# uC_IO.net
KiCad netlist of a schematic drawn in Altium Designer
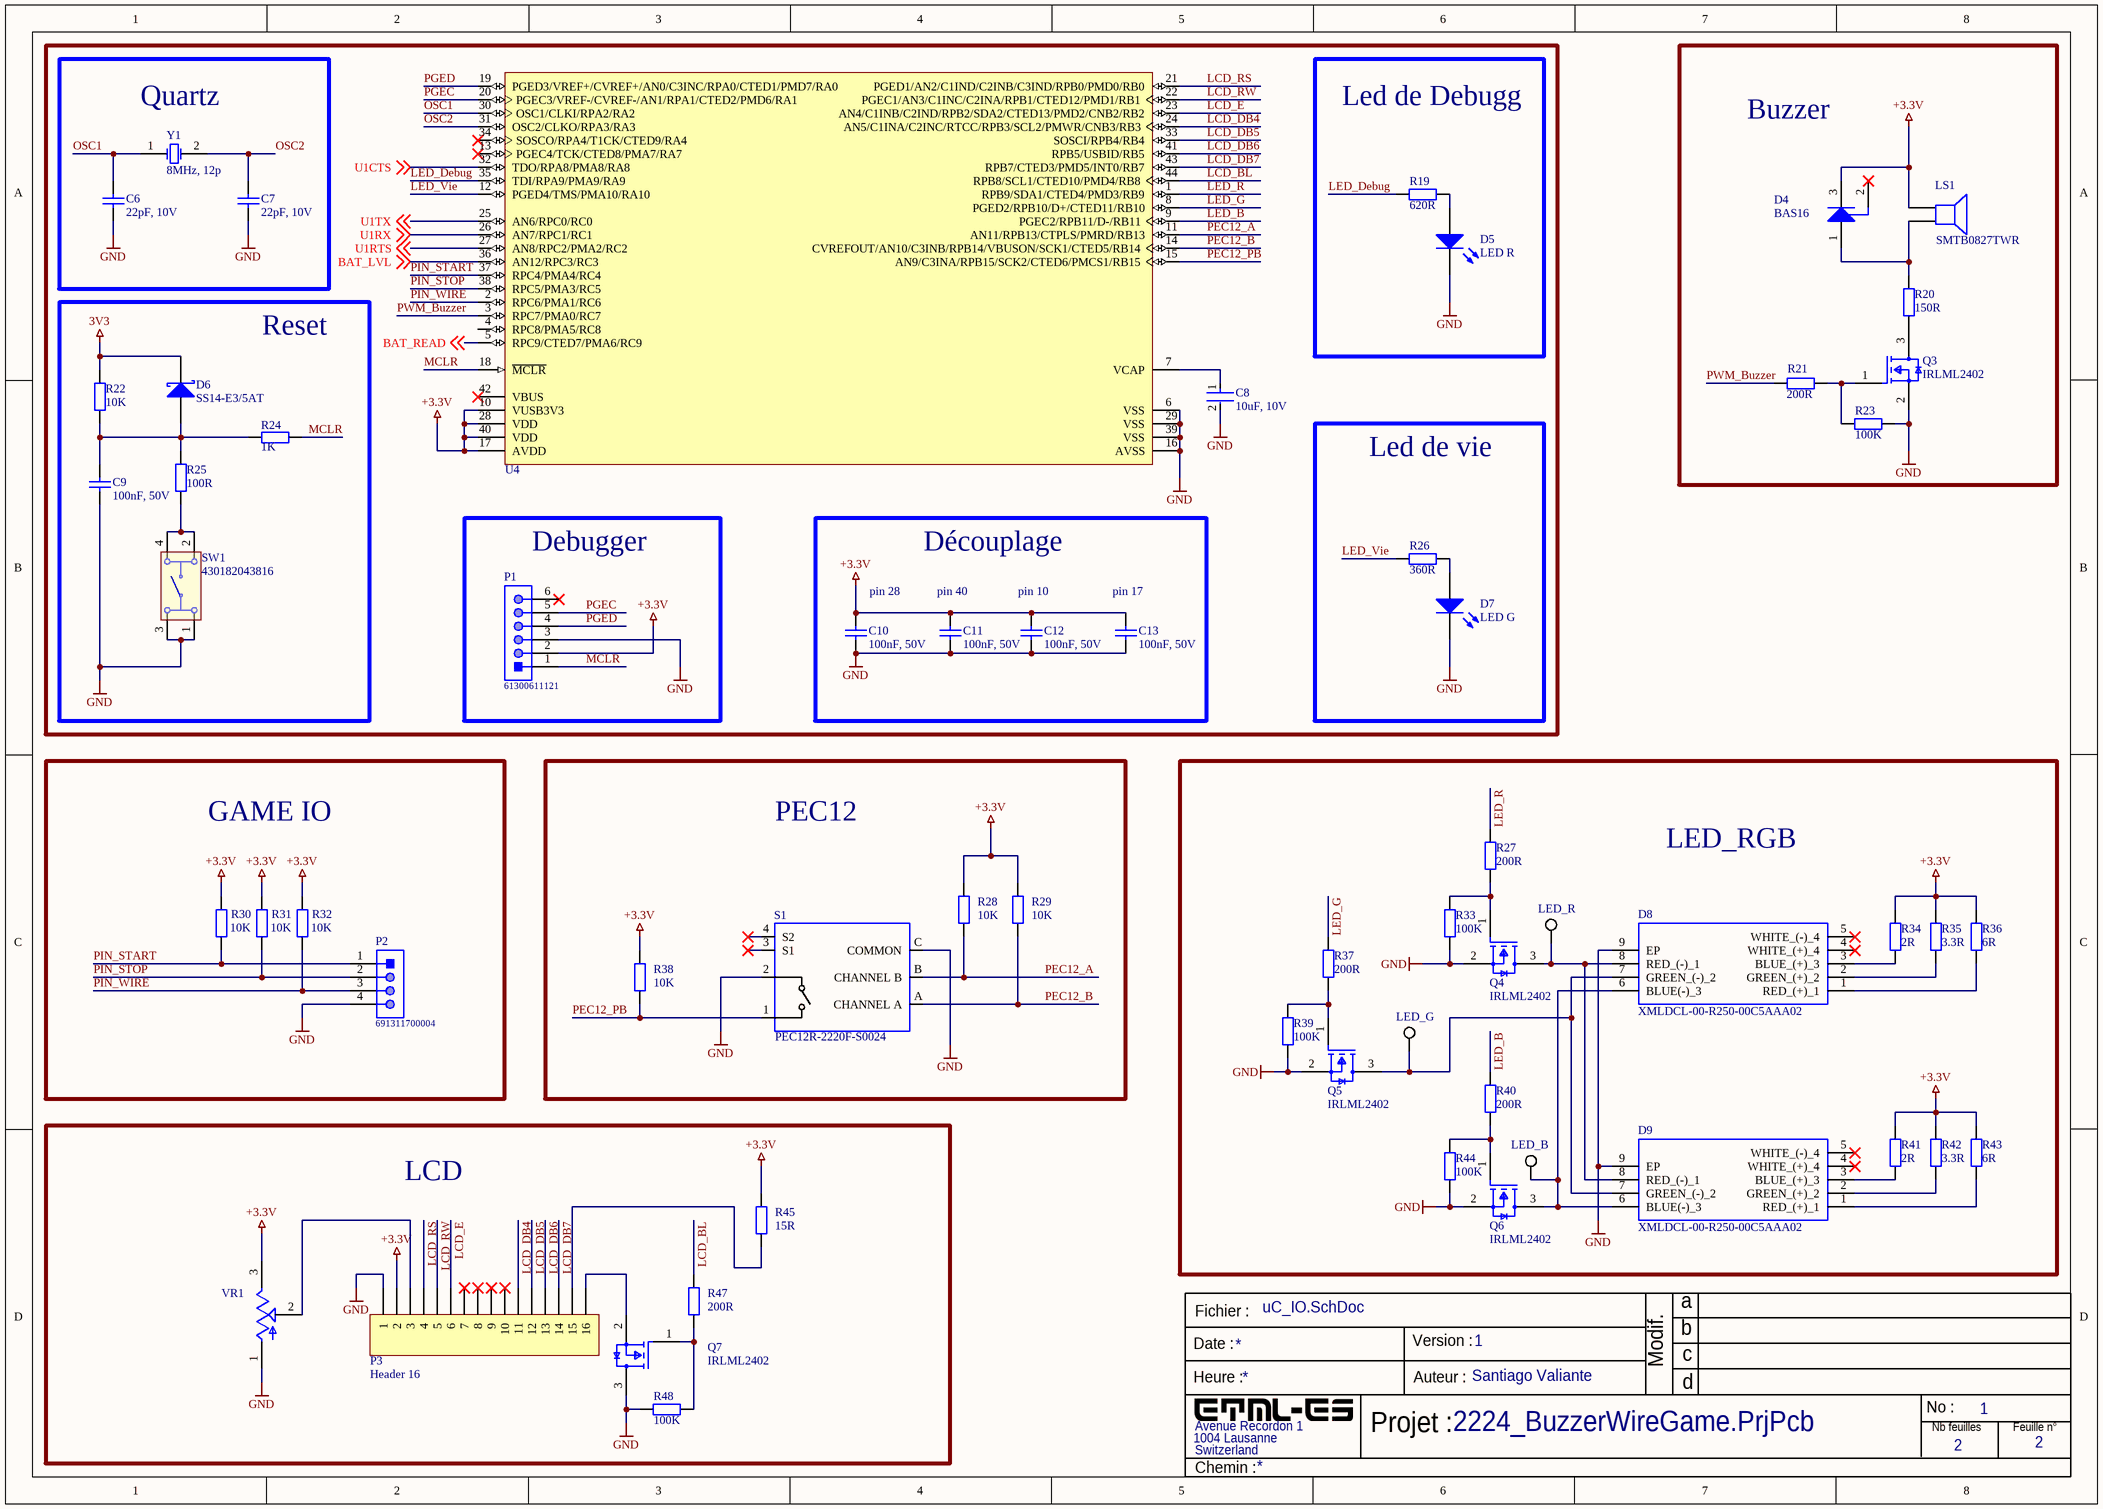
[diagram p0: uC_IO.SchDoc]

(export (version "E")
  (design (tool "Eeschema 10.0.6"))
  (components
    (comp (ref "C6")
      (value "22pF, 10V")
      (footprint "CAP_0805")
      (description "CAP 22pF 10V ±10% 0805 (2012 Metric) Thickness 0.75mm SMD")
      (fields (field (name "TOLERANCE") "Â±10%"))
      (libsource (lib "2121_Robot3roues_V2.0") (part "CAP"))
    )
    (comp (ref "C7")
      (value "22pF, 10V")
      (footprint "CAP_0805")
      (description "CAP 22pF 10V ±10% 0805 (2012 Metric) Thickness 0.75mm SMD")
      (fields (field (name "TOLERANCE") "Â±10%"))
      (libsource (lib "2121_Robot3roues_V2.0") (part "CAP"))
    )
    (comp (ref "C8")
      (value "10uF, 10V")
      (footprint "CAP_0805")
      (description "CAP CER 10UF 10V X5R 0805")
      (fields (field (name "TOLERANCE") "10%") (field (name "MANUFACTURER PART NUMBER") "C0805C106K8PACTU"))
      (libsource (lib "2121_Robot3roues_V2.0") (part "11868f565c42a9108669ba33697ecf6"))
    )
    (comp (ref "C9")
      (value "100nF, 50V")
      (footprint "CAP_0805")
      (description "WCAP-CSGP General Purpose Ceramic Capacitors, size 0805, 100nF, +/-10%, 50VDC")
      (fields (field (name "PART NUMBER") "885012207098") (field (name "PUBLISHER") "Wurth Elektronik"))
      (libsource (lib "VPA_v2b") (part "885012207098"))
    )
    (comp (ref "C10")
      (value "100nF, 50V")
      (footprint "CAP_0805")
      (description "WCAP-CSGP General Purpose Ceramic Capacitors, size 0805, 100nF, +/-10%, 50VDC")
      (fields (field (name "PART NUMBER") "885012207098") (field (name "PUBLISHER") "Wurth Elektronik"))
      (libsource (lib "VPA_v2b") (part "885012207098"))
    )
    (comp (ref "C11")
      (value "100nF, 50V")
      (footprint "CAP_0805")
      (description "WCAP-CSGP General Purpose Ceramic Capacitors, size 0805, 100nF, +/-10%, 50VDC")
      (fields (field (name "PART NUMBER") "885012207098") (field (name "PUBLISHER") "Wurth Elektronik"))
      (libsource (lib "VPA_v2b") (part "885012207098"))
    )
    (comp (ref "C12")
      (value "100nF, 50V")
      (footprint "CAP_0805")
      (description "WCAP-CSGP General Purpose Ceramic Capacitors, size 0805, 100nF, +/-10%, 50VDC")
      (fields (field (name "PART NUMBER") "885012207098") (field (name "PUBLISHER") "Wurth Elektronik"))
      (libsource (lib "VPA_v2b") (part "885012207098"))
    )
    (comp (ref "C13")
      (value "100nF, 50V")
      (footprint "CAP_0805")
      (description "WCAP-CSGP General Purpose Ceramic Capacitors, size 0805, 100nF, +/-10%, 50VDC")
      (fields (field (name "PART NUMBER") "885012207098") (field (name "PUBLISHER") "Wurth Elektronik"))
      (libsource (lib "VPA_v2b") (part "885012207098"))
    )
    (comp (ref "D4")
      (value "BAS16")
      (footprint "INF-SOT23_L")
      (description "Silicon Switching Diode, SOT23, Reel, Green")
      (fields (field (name "MANUFACTURER") "Infineon"))
      (libsource (lib "Altium Content Vault") (part "INF-D_A1K3-3"))
    )
    (comp (ref "D5")
      (value "LED R")
      (footprint "3.2X1.6X1.1")
      (description "Typical RED, GREEN, YELLOW, AMBER GaAs LED")
      (fields (field (name "PUBLISHER") "Altium Limited"))
      (libsource (lib "Miscellaneous Devices") (part "LED2"))
    )
    (comp (ref "D6")
      (value "SS14-E3/5AT")
      (footprint "VISH-DO-214AC-2_V")
      (fields (field (name "MANUFACTURER") "Vishay Semiconductor"))
      (libsource (lib "Altium Content Vault") (part "VISH-DSKY_A1K2-2"))
    )
    (comp (ref "D7")
      (value "LED G")
      (footprint "3.2X1.6X1.1")
      (description "Typical RED, GREEN, YELLOW, AMBER GaAs LED")
      (fields (field (name "PUBLISHER") "Altium Limited"))
      (libsource (lib "Miscellaneous Devices") (part "LED2"))
    )
    (comp (ref "D8")
      (value "XMLDCL-00-R250-00C5AAA02")
      (footprint "XMLDCL00R25000C5AAA02")
      (description "High Power LEDs - Multi-Colour RGB, White 6000K LED")
      (fields (field (name "MOUSER PART NUMBER") "941-XMLDCL0R25C5A02"))
      (libsource (lib "Projet_Lampe_V1") (part "XMLDCL-00-R250-00C5AAA02"))
    )
    (comp (ref "D9")
      (value "XMLDCL-00-R250-00C5AAA02")
      (footprint "XMLDCL00R25000C5AAA02")
      (description "High Power LEDs - Multi-Colour RGB, White 6000K LED")
      (fields (field (name "MOUSER PART NUMBER") "941-XMLDCL0R25C5A02"))
      (libsource (lib "Projet_Lampe_V1") (part "XMLDCL-00-R250-00C5AAA02"))
    )
    (comp (ref "LED_B")
      (value "Vbat")
      (footprint "KSTN-5019_V")
      (description "Test Point, 1 Position SMD, RoHS, Tape and Reel")
      (libsource (lib "Altium Content Vault") (part "TESTPOINT_WHITE"))
    )
    (comp (ref "LED_G")
      (value "Vbat")
      (footprint "KSTN-5019_V")
      (description "Test Point, 1 Position SMD, RoHS, Tape and Reel")
      (libsource (lib "Altium Content Vault") (part "TESTPOINT_WHITE"))
    )
    (comp (ref "LED_R")
      (value "Vbat")
      (footprint "KSTN-5019_V")
      (description "Test Point, 1 Position SMD, RoHS, Tape and Reel")
      (libsource (lib "Altium Content Vault") (part "TESTPOINT_WHITE"))
    )
    (comp (ref "LS1")
      (value "SMTB0827TWR")
      (footprint "XDCR_SMTB-0827-TW-R")
      (description "Loudspeaker")
      (fields (field (name "PUBLISHER") "Altium Limited"))
      (libsource (lib "Miscellaneous Devices") (part "Speaker"))
    )
    (comp (ref "P1")
      (value "61300611121")
      (footprint "61300611121")
      (description "THT Vertical Pin Header WR-PHD, Pitch 2.54 mm, Single Row, 6 pins")
      (fields (field (name "MANUFACTURER") "Wurth Elektronik") (field (name "PUBLISHER") "WurthElektronik"))
      (libsource (lib "Altium Content Vault") (part "WE-CN-1P-M-R6"))
    )
    (comp (ref "P2")
      (value "691311700004")
      (footprint "691311700004")
      (description "Serie 3117 - 5.00mm Open Vertical PCB Header WR-TBL, 4 pin")
      (fields (field (name "MANUFACTURER") "Wurth Elektronik") (field (name "PUBLISHER") "WurthElektronik"))
      (libsource (lib "Altium Content Vault") (part "WE-CN-1P-M-R4"))
    )
    (comp (ref "P3")
      (value "Header 16")
      (footprint "SHDR16W77P254_2X8_2764X859X1004P")
      (description "Header, 16-Pin")
      (fields (field (name "PUBLISHER") "Altium Limited"))
      (libsource (lib "Miscellaneous Connectors") (part "Header 16"))
    )
    (comp (ref "Q3")
      (value "IRLML2402")
      (footprint "FP-Micro3-IPC_B")
      (description "MOSFET N-CH 20V 1.2A SOT-23")
      (libsource (lib "Altium Content Vault") (part "0a9ea7c96deaaede766a5b531c28de0"))
    )
    (comp (ref "Q4")
      (value "IRLML2402")
      (footprint "FP-Micro3-IPC_B")
      (description "MOSFET N-CH 20V 1.2A SOT-23")
      (libsource (lib "Altium Content Vault") (part "0a9ea7c96deaaede766a5b531c28de0"))
    )
    (comp (ref "Q5")
      (value "IRLML2402")
      (footprint "FP-Micro3-IPC_B")
      (description "MOSFET N-CH 20V 1.2A SOT-23")
      (libsource (lib "Altium Content Vault") (part "0a9ea7c96deaaede766a5b531c28de0"))
    )
    (comp (ref "Q6")
      (value "IRLML2402")
      (footprint "FP-Micro3-IPC_B")
      (description "MOSFET N-CH 20V 1.2A SOT-23")
      (libsource (lib "Altium Content Vault") (part "0a9ea7c96deaaede766a5b531c28de0"))
    )
    (comp (ref "Q7")
      (value "IRLML2402")
      (footprint "FP-Micro3-IPC_B")
      (description "MOSFET N-CH 20V 1.2A SOT-23")
      (libsource (lib "Altium Content Vault") (part "0a9ea7c96deaaede766a5b531c28de0"))
    )
    (comp (ref "R19")
      (value "620R")
      (footprint "RES_0805")
      (fields (field (name "PART NUMBER") "ERJ6ENF2703V") (field (name "MANUFACTURER") "Panasonic"))
      (libsource (lib "") (part "RES_1"))
    )
    (comp (ref "R20")
      (value "150R")
      (footprint "RES_0805")
      (description "Resistor")
      (fields (field (name "PUBLISHER") "Altium Limited"))
      (libsource (lib "") (part "Res2_1"))
    )
    (comp (ref "R21")
      (value "200R")
      (footprint "RES_0805")
      (description "Resistor")
      (fields (field (name "PUBLISHER") "Altium Limited"))
      (libsource (lib "Miscellaneous Devices") (part "Res2"))
    )
    (comp (ref "R22")
      (value "10K")
      (footprint "RES_0805")
      (fields (field (name "MANUFACTURER") "Panasonic") (field (name "PART NUMBER") "ERJ-6ENF1002V"))
      (libsource (lib "2121_Robot3roues_V2.0") (part "RES"))
    )
    (comp (ref "R23")
      (value "100K")
      (footprint "RES_0805")
      (description "Resistor")
      (fields (field (name "PUBLISHER") "Altium Limited"))
      (libsource (lib "") (part "Res2_2"))
    )
    (comp (ref "R24")
      (value "1K")
      (footprint "RES_0805")
      (fields (field (name "PART NUMBER") "CRCW08051K00FKEA") (field (name "MANUFACTURER") "Vishay Dale"))
      (libsource (lib "") (part "RES_2"))
    )
    (comp (ref "R25")
      (value "100R")
      (footprint "RES_0805")
      (fields (field (name "MANUFACTURER") "Vishay Dale") (field (name "PART NUMBER") "TNPW0805100RBEEA"))
      (libsource (lib "2121_Robot3roues_V2.0") (part "RES"))
    )
    (comp (ref "R26")
      (value "360R")
      (footprint "RES_0805")
      (fields (field (name "PART NUMBER") "ERJ6ENF2703V") (field (name "MANUFACTURER") "Panasonic"))
      (libsource (lib "") (part "RES_1"))
    )
    (comp (ref "R27")
      (value "200R")
      (footprint "RES_0805")
      (description "Resistor")
      (fields (field (name "PUBLISHER") "Altium Limited"))
      (libsource (lib "Miscellaneous Devices") (part "Res2"))
    )
    (comp (ref "R28")
      (value "10K")
      (footprint "RES_0805")
      (description "Resistor")
      (fields (field (name "PUBLISHER") "Altium Limited"))
      (libsource (lib "") (part "Res2_2"))
    )
    (comp (ref "R29")
      (value "10K")
      (footprint "RES_0805")
      (description "Resistor")
      (fields (field (name "PUBLISHER") "Altium Limited"))
      (libsource (lib "") (part "Res2_2"))
    )
    (comp (ref "R30")
      (value "10K")
      (footprint "RES_0805")
      (description "Resistor")
      (fields (field (name "PUBLISHER") "Altium Limited"))
      (libsource (lib "") (part "Res2_2"))
    )
    (comp (ref "R31")
      (value "10K")
      (footprint "RES_0805")
      (description "Resistor")
      (fields (field (name "PUBLISHER") "Altium Limited"))
      (libsource (lib "") (part "Res2_2"))
    )
    (comp (ref "R32")
      (value "10K")
      (footprint "RES_0805")
      (description "Resistor")
      (fields (field (name "PUBLISHER") "Altium Limited"))
      (libsource (lib "") (part "Res2_2"))
    )
    (comp (ref "R33")
      (value "100K")
      (footprint "RES_0805")
      (description "Resistor")
      (fields (field (name "PUBLISHER") "Altium Limited"))
      (libsource (lib "") (part "Res2_1"))
    )
    (comp (ref "R34")
      (value "2R")
      (footprint "RES_0805")
      (description "Resistor")
      (fields (field (name "PUBLISHER") "Altium Limited"))
      (libsource (lib "") (part "Res2_1"))
    )
    (comp (ref "R35")
      (value "3.3R")
      (footprint "RES_0805")
      (description "Resistor")
      (fields (field (name "PUBLISHER") "Altium Limited"))
      (libsource (lib "") (part "Res2_1"))
    )
    (comp (ref "R36")
      (value "6R")
      (footprint "RES_0805")
      (description "Resistor")
      (fields (field (name "PUBLISHER") "Altium Limited"))
      (libsource (lib "") (part "Res2_1"))
    )
    (comp (ref "R37")
      (value "200R")
      (footprint "RES_0805")
      (description "Resistor")
      (fields (field (name "PUBLISHER") "Altium Limited"))
      (libsource (lib "Miscellaneous Devices") (part "Res2"))
    )
    (comp (ref "R38")
      (value "10K")
      (footprint "RES_0805")
      (description "Resistor")
      (fields (field (name "PUBLISHER") "Altium Limited"))
      (libsource (lib "") (part "Res2_2"))
    )
    (comp (ref "R39")
      (value "100K")
      (footprint "RES_0805")
      (description "Resistor")
      (fields (field (name "PUBLISHER") "Altium Limited"))
      (libsource (lib "") (part "Res2_1"))
    )
    (comp (ref "R40")
      (value "200R")
      (footprint "RES_0805")
      (description "Resistor")
      (fields (field (name "PUBLISHER") "Altium Limited"))
      (libsource (lib "Miscellaneous Devices") (part "Res2"))
    )
    (comp (ref "R41")
      (value "2R")
      (footprint "RES_0805")
      (description "Resistor")
      (fields (field (name "PUBLISHER") "Altium Limited"))
      (libsource (lib "") (part "Res2_1"))
    )
    (comp (ref "R42")
      (value "3.3R")
      (footprint "RES_0805")
      (description "Resistor")
      (fields (field (name "PUBLISHER") "Altium Limited"))
      (libsource (lib "") (part "Res2_1"))
    )
    (comp (ref "R43")
      (value "6R")
      (footprint "RES_0805")
      (description "Resistor")
      (fields (field (name "PUBLISHER") "Altium Limited"))
      (libsource (lib "") (part "Res2_1"))
    )
    (comp (ref "R44")
      (value "100K")
      (footprint "RES_0805")
      (description "Resistor")
      (fields (field (name "PUBLISHER") "Altium Limited"))
      (libsource (lib "") (part "Res2_1"))
    )
    (comp (ref "R45")
      (value "15R")
      (footprint "RES_0805")
      (description "Resistor")
      (fields (field (name "PUBLISHER") "Altium Limited"))
      (libsource (lib "") (part "Res2_2"))
    )
    (comp (ref "R47")
      (value "200R")
      (footprint "RES_0805")
      (description "Resistor")
      (fields (field (name "PUBLISHER") "Altium Limited"))
      (libsource (lib "") (part "Res2_2"))
    )
    (comp (ref "R48")
      (value "100K")
      (footprint "RES_0805")
      (description "Resistor")
      (fields (field (name "PUBLISHER") "Altium Limited"))
      (libsource (lib "") (part "Res2_1"))
    )
    (comp (ref "S1")
      (value "PEC12R-2220F-S0024")
      (footprint "XDCR_PEC12R-2220F-S0024")
      (description "ROTARY ENCODER MECHANICAL 24PPR")
      (libsource (lib "2208_A_JeuSimonInspire") (part "CMP-07421-000062-1"))
    )
    (comp (ref "SW1")
      (value "430182043816")
      (footprint "430182043816")
      (description "WS-TASV SMD Tact Switch 6X6 mm")
      (fields (field (name "MANUFACTURER") "Wuerth Elektronik"))
      (libsource (lib "Altium Content Vault") (part "WE-TACT-SW-4"))
    )
    (comp (ref "U4")
      (value "PIC32MX250F256D-I/PT")
      (footprint "MCHP-TQFP-PT44_M")
      (fields (field (name "PARTNUMBER") "PIC32MX250F128D-I/PT") (field (name "MANUFACTURER") "Microchip"))
      (libsource (lib "Altium Content Vault") (part "MCHP-PIC32MX2XXFXXXD-TQFP-44"))
    )
    (comp (ref "VR1")
      (value "3362P-1-102LF")
      (footprint "TRIM_3362P-1-102LF")
      (description "1 kOhms 0.5W, 1/2W PC Pins Through Hole Trimmer Potentiometer Cermet 1 Turn Top Adjustment")
      (fields (field (name "MF") "Bourns"))
      (libsource (lib "3362P-1-102LF") (part "3362P-1-102LF"))
    )
    (comp (ref "Y1")
      (value "8MHz, 12p")
      (footprint "FOX-FOXSDLF160-20_V")
      (libsource (lib "Altium Content Vault") (part "XTAL_1-2-2"))
    )
  )
  (nets
    (net (code "1") (name "+3.3V") (class "Default")
      (node (ref "C10") (pin "1") (pinfunction "1_1") (pintype "passive"))
      (node (ref "C11") (pin "1") (pinfunction "1_1") (pintype "passive"))
      (node (ref "C12") (pin "1") (pinfunction "1_1") (pintype "passive"))
      (node (ref "C13") (pin "1") (pinfunction "1_1") (pintype "passive"))
      (node (ref "D4") (pin "3") (pinfunction "K_3") (pintype "passive"))
      (node (ref "LS1") (pin "P") (pinfunction "1_P") (pintype "passive"))
      (node (ref "P1") (pin "2") (pinfunction "2_2") (pintype "passive"))
      (node (ref "P3") (pin "2") (pinfunction "2_2") (pintype "passive"))
      (node (ref "R28") (pin "2") (pinfunction "2_2") (pintype "passive"))
      (node (ref "R29") (pin "2") (pinfunction "2_2") (pintype "passive"))
      (node (ref "R30") (pin "2") (pinfunction "2_2") (pintype "passive"))
      (node (ref "R31") (pin "2") (pinfunction "2_2") (pintype "passive"))
      (node (ref "R32") (pin "2") (pinfunction "2_2") (pintype "passive"))
      (node (ref "R34") (pin "1") (pinfunction "1_1") (pintype "passive"))
      (node (ref "R35") (pin "1") (pinfunction "1_1") (pintype "passive"))
      (node (ref "R36") (pin "1") (pinfunction "1_1") (pintype "passive"))
      (node (ref "R38") (pin "2") (pinfunction "2_2") (pintype "passive"))
      (node (ref "R41") (pin "1") (pinfunction "1_1") (pintype "passive"))
      (node (ref "R42") (pin "1") (pinfunction "1_1") (pintype "passive"))
      (node (ref "R43") (pin "1") (pinfunction "1_1") (pintype "passive"))
      (node (ref "R45") (pin "2") (pinfunction "2_2") (pintype "passive"))
      (node (ref "U4") (pin "10") (pinfunction "VUSB3V3_10") (pintype "power_in"))
      (node (ref "U4") (pin "17") (pinfunction "AVDD_17") (pintype "power_in"))
      (node (ref "U4") (pin "28") (pinfunction "VDD_28") (pintype "power_in"))
      (node (ref "U4") (pin "40") (pinfunction "VDD_40") (pintype "power_in"))
      (node (ref "VR1") (pin "3") (pinfunction "CW_3") (pintype "passive"))
    )
    (net (code "2") (name "/LCD_BL") (class "Default")
      (node (ref "R47") (pin "2") (pinfunction "2_2") (pintype "passive"))
      (node (ref "U4") (pin "44") (pinfunction "RPB8/SCL1/CTED10/PMD4/RB8_44") (pintype "bidirectional"))
    )
    (net (code "3") (name "/LCD_DB4") (class "Default")
      (node (ref "P3") (pin "11") (pinfunction "11_11") (pintype "passive"))
      (node (ref "U4") (pin "24") (pinfunction "AN5/C1INA/C2INC/RTCC/RPB3/SCL2/PMWR/CNB3/RB3_24") (pintype "bidirectional"))
    )
    (net (code "4") (name "/LCD_DB5") (class "Default")
      (node (ref "P3") (pin "12") (pinfunction "12_12") (pintype "passive"))
      (node (ref "U4") (pin "33") (pinfunction "SOSCI/RPB4/RB4_33") (pintype "bidirectional"))
    )
    (net (code "5") (name "/LCD_DB6") (class "Default")
      (node (ref "P3") (pin "13") (pinfunction "13_13") (pintype "passive"))
      (node (ref "U4") (pin "41") (pinfunction "RPB5/USBID/RB5_41") (pintype "bidirectional"))
    )
    (net (code "6") (name "/LCD_DB7") (class "Default")
      (node (ref "P3") (pin "14") (pinfunction "14_14") (pintype "passive"))
      (node (ref "U4") (pin "43") (pinfunction "RPB7/CTED3/PMD5/INT0/RB7_43") (pintype "bidirectional"))
    )
    (net (code "7") (name "/LCD_E") (class "Default")
      (node (ref "P3") (pin "6") (pinfunction "6_6") (pintype "passive"))
      (node (ref "U4") (pin "23") (pinfunction "AN4/C1INB/C2IND/RPB2/SDA2/CTED13/PMD2/CNB2/RB2_23") (pintype "bidirectional"))
    )
    (net (code "8") (name "/LCD_RS") (class "Default")
      (node (ref "P3") (pin "4") (pinfunction "4_4") (pintype "passive"))
      (node (ref "U4") (pin "21") (pinfunction "PGED1/AN2/C1IND/C2INB/C3IND/RPB0/PMD0/RB0_21") (pintype "bidirectional"))
    )
    (net (code "9") (name "/LCD_RW") (class "Default")
      (node (ref "P3") (pin "5") (pinfunction "5_5") (pintype "passive"))
      (node (ref "U4") (pin "22") (pinfunction "PGEC1/AN3/C1INC/C2INA/RPB1/CTED12/PMD1/RB1_22") (pintype "bidirectional"))
    )
    (net (code "10") (name "/LED_B") (class "Default")
      (node (ref "R40") (pin "2") (pinfunction "2_2") (pintype "passive"))
      (node (ref "U4") (pin "9") (pinfunction "PGEC2/RPB11/D-/RB11_9") (pintype "bidirectional"))
    )
    (net (code "11") (name "/LED_Debug") (class "Default")
      (node (ref "R19") (pin "2") (pinfunction "2_2") (pintype "passive"))
      (node (ref "U4") (pin "35") (pinfunction "TDI/RPA9/PMA9/RA9_35") (pintype "bidirectional"))
    )
    (net (code "12") (name "/LED_G") (class "Default")
      (node (ref "R37") (pin "2") (pinfunction "2_2") (pintype "passive"))
      (node (ref "U4") (pin "8") (pinfunction "PGED2/RPB10/D+/CTED11/RB10_8") (pintype "bidirectional"))
    )
    (net (code "13") (name "/LED_R") (class "Default")
      (node (ref "R27") (pin "2") (pinfunction "2_2") (pintype "passive"))
      (node (ref "U4") (pin "1") (pinfunction "RPB9/SDA1/CTED4/PMD3/RB9_1") (pintype "bidirectional"))
    )
    (net (code "14") (name "/LED_Vie") (class "Default")
      (node (ref "R26") (pin "2") (pinfunction "2_2") (pintype "passive"))
      (node (ref "U4") (pin "12") (pinfunction "PGED4/TMS/PMA10/RA10_12") (pintype "bidirectional"))
    )
    (net (code "15") (name "/MCLR") (class "Default")
      (node (ref "P1") (pin "1") (pinfunction "1_1") (pintype "passive"))
      (node (ref "R24") (pin "2") (pinfunction "2_2") (pintype "passive"))
      (node (ref "U4") (pin "18") (pinfunction "~{MCLR}_18") (pintype "input"))
    )
    (net (code "16") (name "/OSC1") (class "Default")
      (node (ref "C6") (pin "2") (pinfunction "2_2") (pintype "passive"))
      (node (ref "U4") (pin "30") (pinfunction "OSC1/CLKI/RPA2/RA2_30") (pintype "bidirectional"))
      (node (ref "Y1") (pin "1") (pinfunction "X1_1") (pintype "passive"))
    )
    (net (code "17") (name "/OSC2") (class "Default")
      (node (ref "C7") (pin "2") (pinfunction "2_2") (pintype "passive"))
      (node (ref "U4") (pin "31") (pinfunction "OSC2/CLKO/RPA3/RA3_31") (pintype "bidirectional"))
      (node (ref "Y1") (pin "2") (pinfunction "X2_2") (pintype "passive"))
    )
    (net (code "18") (name "/PEC12_A") (class "Default")
      (node (ref "R28") (pin "1") (pinfunction "1_1") (pintype "passive"))
      (node (ref "S1") (pin "B") (pinfunction "CHANNEL_B_B") (pintype "passive"))
      (node (ref "U4") (pin "11") (pinfunction "AN11/RPB13/CTPLS/PMRD/RB13_11") (pintype "bidirectional"))
    )
    (net (code "19") (name "/PEC12_B") (class "Default")
      (node (ref "R29") (pin "1") (pinfunction "1_1") (pintype "passive"))
      (node (ref "S1") (pin "A") (pinfunction "CHANNEL_A_A") (pintype "passive"))
      (node (ref "U4") (pin "14") (pinfunction "CVREFOUT/AN10/C3INB/RPB14/VBUSON/SCK1/CTED5/RB14_14") (pintype "bidirectional"))
    )
    (net (code "20") (name "/PEC12_PB") (class "Default")
      (node (ref "R38") (pin "1") (pinfunction "1_1") (pintype "passive"))
      (node (ref "S1") (pin "1") (pinfunction "1_1") (pintype "passive"))
      (node (ref "U4") (pin "15") (pinfunction "AN9/C3INA/RPB15/SCK2/CTED6/PMCS1/RB15_15") (pintype "bidirectional"))
    )
    (net (code "21") (name "/PGEC") (class "Default")
      (node (ref "P1") (pin "5") (pinfunction "5_5") (pintype "passive"))
      (node (ref "U4") (pin "20") (pinfunction "PGEC3/VREF-/CVREF-/AN1/RPA1/CTED2/PMD6/RA1_20") (pintype "bidirectional"))
    )
    (net (code "22") (name "/PGED") (class "Default")
      (node (ref "P1") (pin "4") (pinfunction "4_4") (pintype "passive"))
      (node (ref "U4") (pin "19") (pinfunction "PGED3/VREF+/CVREF+/AN0/C3INC/RPA0/CTED1/PMD7/RA0_19") (pintype "bidirectional"))
    )
    (net (code "23") (name "/PIN_START") (class "Default")
      (node (ref "P2") (pin "1") (pinfunction "1_1") (pintype "passive"))
      (node (ref "R30") (pin "1") (pinfunction "1_1") (pintype "passive"))
      (node (ref "U4") (pin "37") (pinfunction "RPC4/PMA4/RC4_37") (pintype "bidirectional"))
    )
    (net (code "24") (name "/PIN_STOP") (class "Default")
      (node (ref "P2") (pin "2") (pinfunction "2_2") (pintype "passive"))
      (node (ref "R31") (pin "1") (pinfunction "1_1") (pintype "passive"))
      (node (ref "U4") (pin "38") (pinfunction "RPC5/PMA3/RC5_38") (pintype "bidirectional"))
    )
    (net (code "25") (name "/PIN_WIRE") (class "Default")
      (node (ref "P2") (pin "3") (pinfunction "3_3") (pintype "passive"))
      (node (ref "R32") (pin "1") (pinfunction "1_1") (pintype "passive"))
      (node (ref "U4") (pin "2") (pinfunction "RPC6/PMA1/RC6_2") (pintype "bidirectional"))
    )
    (net (code "26") (name "/PWM_Buzzer") (class "Default")
      (node (ref "R21") (pin "1") (pinfunction "1_1") (pintype "passive"))
      (node (ref "U4") (pin "3") (pinfunction "RPC7/PMA0/RC7_3") (pintype "bidirectional"))
    )
    (net (code "27") (name "3V3") (class "Default")
      (node (ref "D6") (pin "2") (pinfunction "K_2") (pintype "passive"))
      (node (ref "R22") (pin "2") (pinfunction "2_2") (pintype "passive"))
    )
    (net (code "28") (name "BAT_LVL") (class "Default")
      (node (ref "U4") (pin "36") (pinfunction "AN12/RPC3/RC3_36") (pintype "bidirectional"))
    )
    (net (code "29") (name "BAT_READ") (class "Default")
      (node (ref "U4") (pin "5") (pinfunction "RPC9/CTED7/PMA6/RC9_5") (pintype "bidirectional"))
    )
    (net (code "30") (name "GND") (class "Default")
      (node (ref "C10") (pin "2") (pinfunction "2_2") (pintype "passive"))
      (node (ref "C11") (pin "2") (pinfunction "2_2") (pintype "passive"))
      (node (ref "C12") (pin "2") (pinfunction "2_2") (pintype "passive"))
      (node (ref "C13") (pin "2") (pinfunction "2_2") (pintype "passive"))
      (node (ref "C6") (pin "1") (pinfunction "1_1") (pintype "passive"))
      (node (ref "C7") (pin "1") (pinfunction "1_1") (pintype "passive"))
      (node (ref "C8") (pin "2") (pinfunction "2_2") (pintype "passive"))
      (node (ref "C9") (pin "2") (pinfunction "2_2") (pintype "passive"))
      (node (ref "D5") (pin "2") (pinfunction "K_2") (pintype "passive"))
      (node (ref "D7") (pin "2") (pinfunction "K_2") (pintype "passive"))
      (node (ref "D8") (pin "9") (pinfunction "EP_9") (pintype "passive"))
      (node (ref "D9") (pin "9") (pinfunction "EP_9") (pintype "passive"))
      (node (ref "P1") (pin "3") (pinfunction "3_3") (pintype "passive"))
      (node (ref "P2") (pin "4") (pinfunction "4_4") (pintype "passive"))
      (node (ref "P3") (pin "1") (pinfunction "1_1") (pintype "passive"))
      (node (ref "Q3") (pin "2") (pinfunction "S_2") (pintype "passive"))
      (node (ref "Q4") (pin "2") (pinfunction "S_2") (pintype "passive"))
      (node (ref "Q5") (pin "2") (pinfunction "S_2") (pintype "passive"))
      (node (ref "Q6") (pin "2") (pinfunction "S_2") (pintype "passive"))
      (node (ref "Q7") (pin "3") (pinfunction "D_3") (pintype "passive"))
      (node (ref "R23") (pin "2") (pinfunction "2_2") (pintype "passive"))
      (node (ref "R33") (pin "2") (pinfunction "2_2") (pintype "passive"))
      (node (ref "R39") (pin "2") (pinfunction "2_2") (pintype "passive"))
      (node (ref "R44") (pin "2") (pinfunction "2_2") (pintype "passive"))
      (node (ref "R48") (pin "2") (pinfunction "2_2") (pintype "passive"))
      (node (ref "S1") (pin "2") (pinfunction "2_2") (pintype "passive"))
      (node (ref "S1") (pin "C") (pinfunction "COMMON_C") (pintype "passive"))
      (node (ref "SW1") (pin "1") (pinfunction "1_1") (pintype "passive"))
      (node (ref "SW1") (pin "3") (pinfunction "3_3") (pintype "passive"))
      (node (ref "U4") (pin "16") (pinfunction "AVSS_16") (pintype "power_in"))
      (node (ref "U4") (pin "29") (pinfunction "VSS_29") (pintype "power_in"))
      (node (ref "U4") (pin "39") (pinfunction "VSS_39") (pintype "power_in"))
      (node (ref "U4") (pin "6") (pinfunction "VSS_6") (pintype "power_in"))
      (node (ref "VR1") (pin "1") (pinfunction "CCW_1") (pintype "passive"))
    )
    (net (code "31") (name "Net-(D4-A)") (class "Default")
      (node (ref "D4") (pin "1") (pinfunction "A_1") (pintype "passive"))
      (node (ref "LS1") (pin "N") (pinfunction "2_N") (pintype "passive"))
      (node (ref "R20") (pin "1") (pinfunction "1_1") (pintype "passive"))
    )
    (net (code "32") (name "Net-(D5-A)") (class "Default")
      (node (ref "D5") (pin "1") (pinfunction "A_1") (pintype "passive"))
      (node (ref "R19") (pin "1") (pinfunction "1_1") (pintype "passive"))
    )
    (net (code "33") (name "Net-(D6-A)") (class "Default")
      (node (ref "C9") (pin "1") (pinfunction "1_1") (pintype "passive"))
      (node (ref "D6") (pin "1") (pinfunction "A_1") (pintype "passive"))
      (node (ref "R22") (pin "1") (pinfunction "1_1") (pintype "passive"))
      (node (ref "R24") (pin "1") (pinfunction "1_1") (pintype "passive"))
      (node (ref "R25") (pin "2") (pinfunction "2_2") (pintype "passive"))
    )
    (net (code "34") (name "Net-(D7-A)") (class "Default")
      (node (ref "D7") (pin "1") (pinfunction "A_1") (pintype "passive"))
      (node (ref "R26") (pin "1") (pinfunction "1_1") (pintype "passive"))
    )
    (net (code "35") (name "Net-(D8-BLUE(-)_3)") (class "Default")
      (node (ref "D8") (pin "6") (pinfunction "BLUE(-)_3_6") (pintype "passive"))
      (node (ref "D9") (pin "6") (pinfunction "BLUE(-)_3_6") (pintype "passive"))
      (node (ref "LED_B") (pin "1") (pinfunction "1_1") (pintype "passive"))
      (node (ref "Q6") (pin "3") (pinfunction "D_3") (pintype "passive"))
    )
    (net (code "36") (name "Net-(D8-BLUE_(+)_3)") (class "Default")
      (node (ref "D8") (pin "3") (pinfunction "BLUE_(+)_3_3") (pintype "passive"))
      (node (ref "R34") (pin "2") (pinfunction "2_2") (pintype "passive"))
    )
    (net (code "37") (name "Net-(D8-GREEN_(+)_2)") (class "Default")
      (node (ref "D8") (pin "2") (pinfunction "GREEN_(+)_2_2") (pintype "passive"))
      (node (ref "R35") (pin "2") (pinfunction "2_2") (pintype "passive"))
    )
    (net (code "38") (name "Net-(D8-GREEN_(-)_2)") (class "Default")
      (node (ref "D8") (pin "7") (pinfunction "GREEN_(-)_2_7") (pintype "passive"))
      (node (ref "D9") (pin "7") (pinfunction "GREEN_(-)_2_7") (pintype "passive"))
      (node (ref "LED_G") (pin "1") (pinfunction "1_1") (pintype "passive"))
      (node (ref "Q5") (pin "3") (pinfunction "D_3") (pintype "passive"))
    )
    (net (code "39") (name "Net-(D8-RED_(+)_1)") (class "Default")
      (node (ref "D8") (pin "1") (pinfunction "RED_(+)_1_1") (pintype "passive"))
      (node (ref "R36") (pin "2") (pinfunction "2_2") (pintype "passive"))
    )
    (net (code "40") (name "Net-(D8-RED_(-)_1)") (class "Default")
      (node (ref "D8") (pin "8") (pinfunction "RED_(-)_1_8") (pintype "passive"))
      (node (ref "D9") (pin "8") (pinfunction "RED_(-)_1_8") (pintype "passive"))
      (node (ref "LED_R") (pin "1") (pinfunction "1_1") (pintype "passive"))
      (node (ref "Q4") (pin "3") (pinfunction "D_3") (pintype "passive"))
    )
    (net (code "41") (name "Net-(D9-BLUE_(+)_3)") (class "Default")
      (node (ref "D9") (pin "3") (pinfunction "BLUE_(+)_3_3") (pintype "passive"))
      (node (ref "R41") (pin "2") (pinfunction "2_2") (pintype "passive"))
    )
    (net (code "42") (name "Net-(D9-GREEN_(+)_2)") (class "Default")
      (node (ref "D9") (pin "2") (pinfunction "GREEN_(+)_2_2") (pintype "passive"))
      (node (ref "R42") (pin "2") (pinfunction "2_2") (pintype "passive"))
    )
    (net (code "43") (name "Net-(D9-RED_(+)_1)") (class "Default")
      (node (ref "D9") (pin "1") (pinfunction "RED_(+)_1_1") (pintype "passive"))
      (node (ref "R43") (pin "2") (pinfunction "2_2") (pintype "passive"))
    )
    (net (code "44") (name "Net-(P3-Pad15)") (class "Default")
      (node (ref "P3") (pin "15") (pinfunction "15_15") (pintype "passive"))
      (node (ref "R45") (pin "1") (pinfunction "1_1") (pintype "passive"))
    )
    (net (code "45") (name "Net-(Q3-D)") (class "Default")
      (node (ref "Q3") (pin "3") (pinfunction "D_3") (pintype "passive"))
      (node (ref "R20") (pin "2") (pinfunction "2_2") (pintype "passive"))
    )
    (net (code "46") (name "Net-(Q3-G)") (class "Default")
      (node (ref "Q3") (pin "1") (pinfunction "G_1") (pintype "passive"))
      (node (ref "R21") (pin "2") (pinfunction "2_2") (pintype "passive"))
      (node (ref "R23") (pin "1") (pinfunction "1_1") (pintype "passive"))
    )
    (net (code "47") (name "Net-(Q4-G)") (class "Default")
      (node (ref "Q4") (pin "1") (pinfunction "G_1") (pintype "passive"))
      (node (ref "R27") (pin "1") (pinfunction "1_1") (pintype "passive"))
      (node (ref "R33") (pin "1") (pinfunction "1_1") (pintype "passive"))
    )
    (net (code "48") (name "Net-(Q5-G)") (class "Default")
      (node (ref "Q5") (pin "1") (pinfunction "G_1") (pintype "passive"))
      (node (ref "R37") (pin "1") (pinfunction "1_1") (pintype "passive"))
      (node (ref "R39") (pin "1") (pinfunction "1_1") (pintype "passive"))
    )
    (net (code "49") (name "Net-(Q6-G)") (class "Default")
      (node (ref "Q6") (pin "1") (pinfunction "G_1") (pintype "passive"))
      (node (ref "R40") (pin "1") (pinfunction "1_1") (pintype "passive"))
      (node (ref "R44") (pin "1") (pinfunction "1_1") (pintype "passive"))
    )
    (net (code "50") (name "Net-(Q7-G)") (class "Default")
      (node (ref "Q7") (pin "1") (pinfunction "G_1") (pintype "passive"))
      (node (ref "R47") (pin "1") (pinfunction "1_1") (pintype "passive"))
      (node (ref "R48") (pin "1") (pinfunction "1_1") (pintype "passive"))
    )
    (net (code "51") (name "Net-(Q7-S)") (class "Default")
      (node (ref "P3") (pin "16") (pinfunction "16_16") (pintype "passive"))
      (node (ref "Q7") (pin "2") (pinfunction "S_2") (pintype "passive"))
    )
    (net (code "52") (name "Net-(R25-Pad1)") (class "Default")
      (node (ref "R25") (pin "1") (pinfunction "1_1") (pintype "passive"))
      (node (ref "SW1") (pin "2") (pinfunction "2_2") (pintype "passive"))
      (node (ref "SW1") (pin "4") (pinfunction "4_4") (pintype "passive"))
    )
    (net (code "53") (name "Net-(U4-VCAP)") (class "Default")
      (node (ref "C8") (pin "1") (pinfunction "1_1") (pintype "passive"))
      (node (ref "U4") (pin "7") (pinfunction "VCAP_7") (pintype "passive"))
    )
    (net (code "54") (name "Net-(VR1-WIPER)") (class "Default")
      (node (ref "P3") (pin "3") (pinfunction "3_3") (pintype "passive"))
      (node (ref "VR1") (pin "2") (pinfunction "WIPER_2") (pintype "passive"))
    )
    (net (code "55") (name "U1CTS") (class "Default")
      (node (ref "U4") (pin "32") (pinfunction "TDO/RPA8/PMA8/RA8_32") (pintype "bidirectional"))
    )
    (net (code "56") (name "U1RTS") (class "Default")
      (node (ref "U4") (pin "27") (pinfunction "AN8/RPC2/PMA2/RC2_27") (pintype "bidirectional"))
    )
    (net (code "57") (name "U1RX") (class "Default")
      (node (ref "U4") (pin "26") (pinfunction "AN7/RPC1/RC1_26") (pintype "bidirectional"))
    )
    (net (code "58") (name "U1TX") (class "Default")
      (node (ref "U4") (pin "25") (pinfunction "AN6/RPC0/RC0_25") (pintype "bidirectional"))
    )
    (net (code "59") (name "unconnected-(D4-NC-Pad2)") (class "Default")
      (node (ref "D4") (pin "2") (pinfunction "NC_2") (pintype "passive+no_connect"))
    )
    (net (code "60") (name "unconnected-(D8-WHITE_(+)_4-Pad4)") (class "Default")
      (node (ref "D8") (pin "4") (pinfunction "WHITE_(+)_4_4") (pintype "passive+no_connect"))
    )
    (net (code "61") (name "unconnected-(D8-WHITE_(-)_4-Pad5)") (class "Default")
      (node (ref "D8") (pin "5") (pinfunction "WHITE_(-)_4_5") (pintype "passive+no_connect"))
    )
    (net (code "62") (name "unconnected-(D9-WHITE_(+)_4-Pad4)") (class "Default")
      (node (ref "D9") (pin "4") (pinfunction "WHITE_(+)_4_4") (pintype "passive+no_connect"))
    )
    (net (code "63") (name "unconnected-(D9-WHITE_(-)_4-Pad5)") (class "Default")
      (node (ref "D9") (pin "5") (pinfunction "WHITE_(-)_4_5") (pintype "passive+no_connect"))
    )
    (net (code "64") (name "unconnected-(P1-Pad6)") (class "Default")
      (node (ref "P1") (pin "6") (pinfunction "6_6") (pintype "passive+no_connect"))
    )
    (net (code "65") (name "unconnected-(P3-Pad7)") (class "Default")
      (node (ref "P3") (pin "7") (pinfunction "7_7") (pintype "passive+no_connect"))
    )
    (net (code "66") (name "unconnected-(P3-Pad8)") (class "Default")
      (node (ref "P3") (pin "8") (pinfunction "8_8") (pintype "passive+no_connect"))
    )
    (net (code "67") (name "unconnected-(P3-Pad9)") (class "Default")
      (node (ref "P3") (pin "9") (pinfunction "9_9") (pintype "passive+no_connect"))
    )
    (net (code "68") (name "unconnected-(P3-Pad10)") (class "Default")
      (node (ref "P3") (pin "10") (pinfunction "10_10") (pintype "passive+no_connect"))
    )
    (net (code "69") (name "unconnected-(S1-S1-Pad3)") (class "Default")
      (node (ref "S1") (pin "3") (pinfunction "S1_3") (pintype "passive+no_connect"))
    )
    (net (code "70") (name "unconnected-(S1-S2-Pad4)") (class "Default")
      (node (ref "S1") (pin "4") (pinfunction "S2_4") (pintype "passive+no_connect"))
    )
    (net (code "71") (name "unconnected-(U4-PGEC4{slash}TCK{slash}CTED8{slash}PMA7{slash}RA7-Pad13)") (class "Default")
      (node (ref "U4") (pin "13") (pinfunction "PGEC4/TCK/CTED8/PMA7/RA7_13") (pintype "bidirectional+no_connect"))
    )
    (net (code "72") (name "unconnected-(U4-RPC8{slash}PMA5{slash}RC8-Pad4)") (class "Default")
      (node (ref "U4") (pin "4") (pinfunction "RPC8/PMA5/RC8_4") (pintype "bidirectional"))
    )
    (net (code "73") (name "unconnected-(U4-SOSCO{slash}RPA4{slash}T1CK{slash}CTED9{slash}RA4-Pad34)") (class "Default")
      (node (ref "U4") (pin "34") (pinfunction "SOSCO/RPA4/T1CK/CTED9/RA4_34") (pintype "bidirectional+no_connect"))
    )
    (net (code "74") (name "unconnected-(U4-VBUS-Pad42)") (class "Default")
      (node (ref "U4") (pin "42") (pinfunction "VBUS_42") (pintype "power_in+no_connect"))
    )
  )
)
